# GlowStarter.net
KiCad netlist of a schematic drawn in EAGLE
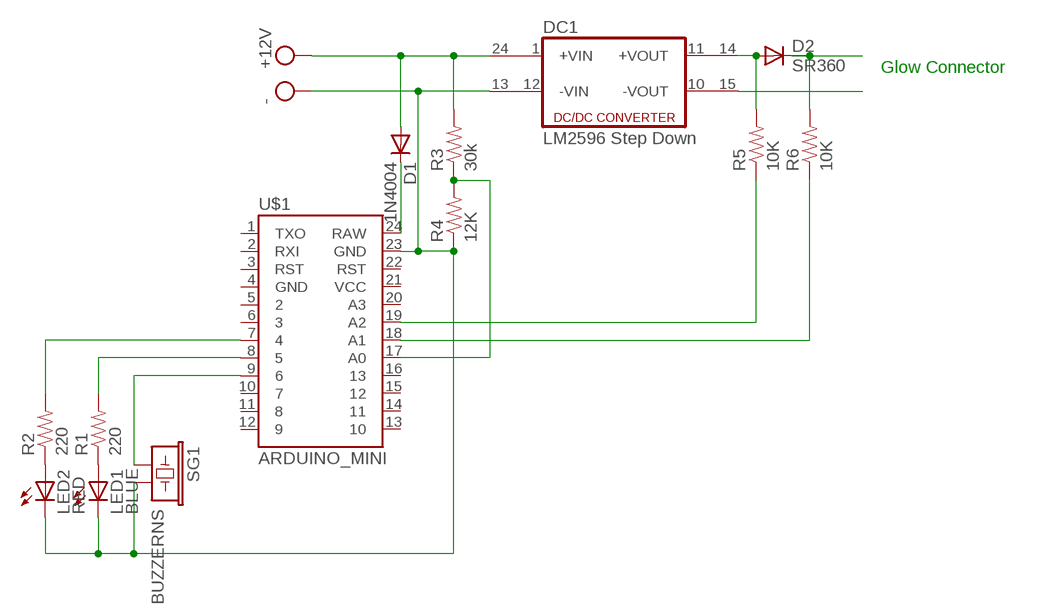
[diagram p0: schematic, sheet 1]

(export (version "E")
  (design (tool "Eeschema 10.0.6"))
  (components
    (comp (ref "D1")
      (value "1N4004")
      (footprint "eagle-import:DO41-10")
      (libsource (lib "eagle-import") (part "1N4004"))
    )
    (comp (ref "D2")
      (value "SR360")
      (footprint "eagle-import:DO201-15")
      (libsource (lib "eagle-import") (part "SB320"))
    )
    (comp (ref "DC1")
      (value "LM2596 Step Down")
      (footprint "eagle-import:CMK")
      (libsource (lib "eagle-import") (part "DC213R"))
    )
    (comp (ref "LED1")
      (value "BLUE")
      (footprint "eagle-import:LED_LD260")
      (libsource (lib "eagle-import") (part "LED_ELD260"))
    )
    (comp (ref "LED2")
      (value "RED")
      (footprint "eagle-import:LED_LD260")
      (libsource (lib "eagle-import") (part "LED_ELD260"))
    )
    (comp (ref "R1")
      (value "220")
      (footprint "eagle-import:AXIAL-0.3-KIT")
      (libsource (lib "eagle-import") (part "RESISTORKIT"))
    )
    (comp (ref "R2")
      (value "220")
      (footprint "eagle-import:AXIAL-0.3-KIT")
      (libsource (lib "eagle-import") (part "RESISTORKIT"))
    )
    (comp (ref "R3")
      (value "30k")
      (footprint "eagle-import:AXIAL-0.3-KIT")
      (libsource (lib "eagle-import") (part "RESISTORKIT"))
    )
    (comp (ref "R4")
      (value "12K")
      (footprint "eagle-import:AXIAL-0.3-KIT")
      (libsource (lib "eagle-import") (part "RESISTORKIT"))
    )
    (comp (ref "R5")
      (value "10K")
      (footprint "eagle-import:AXIAL-0.3-KIT")
      (libsource (lib "eagle-import") (part "RESISTORKIT"))
    )
    (comp (ref "R6")
      (value "10K")
      (footprint "eagle-import:AXIAL-0.3-KIT")
      (libsource (lib "eagle-import") (part "RESISTORKIT"))
    )
    (comp (ref "SG1")
      (value "BUZZERNS")
      (footprint "eagle-import:BUZZER-12MM-NS")
      (libsource (lib "eagle-import") (part "BUZZERNS"))
    )
    (comp (ref "U$1")
      (value "ARDUINO_MINI")
      (footprint "eagle-import:ARDUINO_MINI")
      (libsource (lib "eagle-import") (part "ARDUINO_MINI"))
    )
  )
  (nets
    (net (code "1") (name "+12V") (class "Default")
      (node (ref "D1") (pin "A") (pinfunction "A_A") (pintype "passive"))
      (node (ref "DC1") (pin "13") (pinfunction "-VIN1_13") (pintype "passive"))
      (node (ref "DC1") (pin "24") (pinfunction "+VIN1_24") (pintype "passive"))
      (node (ref "LED1") (pin "K") (pinfunction "C_K") (pintype "passive"))
      (node (ref "LED2") (pin "K") (pinfunction "C_K") (pintype "passive"))
      (node (ref "R3") (pin "P$2") (pinfunction "2_P$2") (pintype "passive"))
      (node (ref "R4") (pin "P$1") (pinfunction "1_P$1") (pintype "passive"))
      (node (ref "SG1") (pin "-") (pinfunction "2_-") (pintype "passive"))
      (node (ref "U$1") (pin "23") (pinfunction "GND_23") (pintype "bidirectional"))
    )
    (net (code "2") (name "Net-(DC1-+VOUT1)") (class "Default")
      (node (ref "D2") (pin "A") (pinfunction "A_A") (pintype "passive"))
      (node (ref "DC1") (pin "14") (pinfunction "+VOUT1_14") (pintype "passive"))
      (node (ref "R5") (pin "P$2") (pinfunction "2_P$2") (pintype "passive"))
    )
    (net (code "3") (name "Net-(R1-1)") (class "Default")
      (node (ref "LED1") (pin "A") (pinfunction "A_A") (pintype "passive"))
      (node (ref "R1") (pin "P$1") (pinfunction "1_P$1") (pintype "passive"))
    )
    (net (code "4") (name "Net-(R1-2)") (class "Default")
      (node (ref "R1") (pin "P$2") (pinfunction "2_P$2") (pintype "passive"))
      (node (ref "U$1") (pin "8") (pinfunction "5_8") (pintype "bidirectional"))
    )
    (net (code "5") (name "Net-(R2-1)") (class "Default")
      (node (ref "LED2") (pin "A") (pinfunction "A_A") (pintype "passive"))
      (node (ref "R2") (pin "P$1") (pinfunction "1_P$1") (pintype "passive"))
    )
    (net (code "6") (name "Net-(R2-2)") (class "Default")
      (node (ref "R2") (pin "P$2") (pinfunction "2_P$2") (pintype "passive"))
      (node (ref "U$1") (pin "7") (pinfunction "4_7") (pintype "bidirectional"))
    )
    (net (code "7") (name "Net-(R3-1)") (class "Default")
      (node (ref "R3") (pin "P$1") (pinfunction "1_P$1") (pintype "passive"))
      (node (ref "R4") (pin "P$2") (pinfunction "2_P$2") (pintype "passive"))
      (node (ref "U$1") (pin "17") (pinfunction "A0_17") (pintype "bidirectional"))
    )
    (net (code "8") (name "Net-(R5-1)") (class "Default")
      (node (ref "R5") (pin "P$1") (pinfunction "1_P$1") (pintype "passive"))
      (node (ref "U$1") (pin "19") (pinfunction "A2_19") (pintype "bidirectional"))
    )
    (net (code "9") (name "Net-(R6-1)") (class "Default")
      (node (ref "R6") (pin "P$1") (pinfunction "1_P$1") (pintype "passive"))
      (node (ref "U$1") (pin "18") (pinfunction "A1_18") (pintype "bidirectional"))
    )
    (net (code "10") (name "Net-(R6-2)") (class "Default")
      (node (ref "D2") (pin "C") (pinfunction "C_C") (pintype "passive"))
      (node (ref "R6") (pin "P$2") (pinfunction "2_P$2") (pintype "passive"))
    )
    (net (code "11") (name "Net-(SG1-1)") (class "Default")
      (node (ref "SG1") (pin "+") (pinfunction "1_+") (pintype "passive"))
      (node (ref "U$1") (pin "9") (pinfunction "6_9") (pintype "bidirectional"))
    )
    (net (code "12") (name "Net-(U$1-RAW)") (class "Default")
      (node (ref "D1") (pin "C") (pinfunction "C_C") (pintype "passive"))
      (node (ref "U$1") (pin "24") (pinfunction "RAW_24") (pintype "bidirectional"))
    )
    (net (code "13") (name "unconnected-(DC1-+VIN-Pad1)") (class "Default")
      (node (ref "DC1") (pin "1") (pinfunction "+VIN_1") (pintype "passive"))
    )
    (net (code "14") (name "unconnected-(DC1-+VOUT-Pad11)") (class "Default")
      (node (ref "DC1") (pin "11") (pinfunction "+VOUT_11") (pintype "passive"))
    )
    (net (code "15") (name "unconnected-(DC1--VIN-Pad12)") (class "Default")
      (node (ref "DC1") (pin "12") (pinfunction "-VIN_12") (pintype "passive"))
    )
    (net (code "16") (name "unconnected-(DC1--VOUT-Pad10)") (class "Default")
      (node (ref "DC1") (pin "10") (pinfunction "-VOUT_10") (pintype "passive"))
    )
    (net (code "17") (name "unconnected-(DC1--VOUT1-Pad15)") (class "Default")
      (node (ref "DC1") (pin "15") (pinfunction "-VOUT1_15") (pintype "passive"))
    )
    (net (code "18") (name "unconnected-(U$1-2-Pad5)") (class "Default")
      (node (ref "U$1") (pin "5") (pinfunction "2_5") (pintype "bidirectional"))
    )
    (net (code "19") (name "unconnected-(U$1-3-Pad6)") (class "Default")
      (node (ref "U$1") (pin "6") (pinfunction "3_6") (pintype "bidirectional"))
    )
    (net (code "20") (name "unconnected-(U$1-7-Pad10)") (class "Default")
      (node (ref "U$1") (pin "10") (pinfunction "7_10") (pintype "bidirectional"))
    )
    (net (code "21") (name "unconnected-(U$1-8-Pad11)") (class "Default")
      (node (ref "U$1") (pin "11") (pinfunction "8_11") (pintype "bidirectional"))
    )
    (net (code "22") (name "unconnected-(U$1-9-Pad12)") (class "Default")
      (node (ref "U$1") (pin "12") (pinfunction "9_12") (pintype "bidirectional"))
    )
    (net (code "23") (name "unconnected-(U$1-10-Pad13)") (class "Default")
      (node (ref "U$1") (pin "13") (pinfunction "10_13") (pintype "bidirectional"))
    )
    (net (code "24") (name "unconnected-(U$1-11-Pad14)") (class "Default")
      (node (ref "U$1") (pin "14") (pinfunction "11_14") (pintype "bidirectional"))
    )
    (net (code "25") (name "unconnected-(U$1-12-Pad15)") (class "Default")
      (node (ref "U$1") (pin "15") (pinfunction "12_15") (pintype "bidirectional"))
    )
    (net (code "26") (name "unconnected-(U$1-13-Pad16)") (class "Default")
      (node (ref "U$1") (pin "16") (pinfunction "13_16") (pintype "bidirectional"))
    )
    (net (code "27") (name "unconnected-(U$1-A3-Pad20)") (class "Default")
      (node (ref "U$1") (pin "20") (pinfunction "A3_20") (pintype "bidirectional"))
    )
    (net (code "28") (name "unconnected-(U$1-GND-Pad4)") (class "Default")
      (node (ref "U$1") (pin "4") (pinfunction "GND_4") (pintype "bidirectional"))
    )
    (net (code "29") (name "unconnected-(U$1-RST-Pad3)") (class "Default")
      (node (ref "U$1") (pin "3") (pinfunction "RST_3") (pintype "bidirectional"))
    )
    (net (code "30") (name "unconnected-(U$1-RST-Pad22)") (class "Default")
      (node (ref "U$1") (pin "22") (pinfunction "RST_22") (pintype "bidirectional"))
    )
    (net (code "31") (name "unconnected-(U$1-RXI-Pad2)") (class "Default")
      (node (ref "U$1") (pin "2") (pinfunction "RXI_2") (pintype "bidirectional"))
    )
    (net (code "32") (name "unconnected-(U$1-TXO-Pad1)") (class "Default")
      (node (ref "U$1") (pin "1") (pinfunction "TXO_1") (pintype "bidirectional"))
    )
    (net (code "33") (name "unconnected-(U$1-VCC-Pad21)") (class "Default")
      (node (ref "U$1") (pin "21") (pinfunction "VCC_21") (pintype "bidirectional"))
    )
  )
)
